# 5Vto3V3Buck.net
KiCad netlist of a schematic drawn in Altium Designer
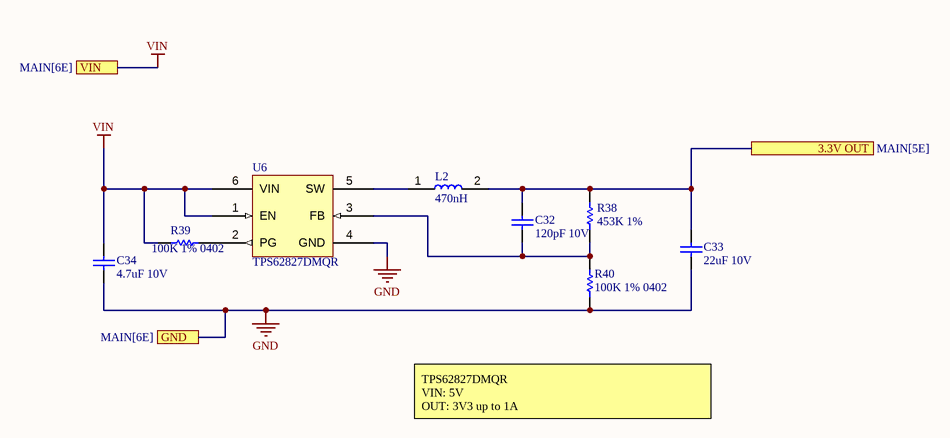
[diagram p0: 5Vto3V3Buck.SchDoc]

(export (version "E")
  (design (tool "Eeschema 10.0.6"))
  (components
    (comp (ref "C32")
      (value "120pF 10V")
      (footprint "CAPC0603(1608)100_N")
      (description "CAP 120pF 10V ±10% 0603 (1608 Metric) Thickness 1mm SMD")
      (fields (field (name "TOLERANCE") "Â±10%"))
      (libsource (lib "Altium Content Vault") (part "CAP"))
    )
    (comp (ref "C33")
      (value "22uF 10V")
      (footprint "CAPC1608X100X20ML10")
      (description "Chip Capacitor, 22 uF, +/- 20%, 10 V, -55 to 85 degC, 0603 (1608 Metric), RoHS, Tape and Reel")
      (fields (field (name "MANUFACTURER") "TDK") (field (name "TOLERANCE") "±20%"))
      (libsource (lib "Altium Content Vault") (part "CAP-NP-2"))
    )
    (comp (ref "C34")
      (value "4.7uF 10V")
      (footprint "CAPC0603(1608)55_N")
      (description "CAP 4.7uF 10V ±10% 0603 (1608 Metric) Thickness 0.55mm SMD")
      (fields (field (name "TOLERANCE") "Â±10%"))
      (libsource (lib "Altium Content Vault") (part "CAP"))
    )
    (comp (ref "L2")
      (value "470nH")
      (footprint "MLP2012SR47MT0S1")
      (description "FIXED IND 470NH 1.2A 90 MOHM SMD")
      (fields (field (name "MP") "MLP2012SR47MT0S1") (field (name "MANUFACTURER") "TDK"))
      (libsource (lib "ESE516A2") (part "MLP2012SR47MT0S1"))
    )
    (comp (ref "R38")
      (value "453K 1%")
      (footprint "RESC0402(1005)_L")
      (description "453K 0.063W 1% 0402 (1005 Metric)  SMD")
      (fields (field (name "TOLERANCE") "1 %") (field (name "POWER") "0.063 W"))
      (libsource (lib "Altium Content Vault") (part "RES"))
    )
    (comp (ref "R39")
      (value "100K 1% 0402")
      (footprint "RESC0402(1005)_M")
      (description "100K 0.063W 1% 0402 (1005 Metric)  SMD")
      (fields (field (name "POWER") "0.063 W") (field (name "TOLERANCE") "1 %"))
      (libsource (lib "Altium Content Vault") (part "RES"))
    )
    (comp (ref "R40")
      (value "100K 1% 0402")
      (footprint "RESC0402(1005)_M")
      (description "100K 0.063W 1% 0402 (1005 Metric)  SMD")
      (fields (field (name "POWER") "0.063 W") (field (name "TOLERANCE") "1 %"))
      (libsource (lib "Altium Content Vault") (part "RES"))
    )
    (comp (ref "U6")
      (value "TPS62827DMQR")
      (footprint "Texas_Instruments_DMQ0006A_MFG")
      (description "2.4V-5.5V input, 4A step-down converter with 1% Accuracy in 1.5mm x 1.5mm QFN 6-VSON-HR -40 to 125")
      (fields (field (name "MANUFACTURER") "Texas Instruments"))
      (libsource (lib "ESE516A2") (part "TPS62827DMQR"))
    )
  )
  (nets
    (net (code "1") (name "/3.3V OUT") (class "Default")
      (node (ref "C32") (pin "2") (pinfunction "2_2") (pintype "passive"))
      (node (ref "C33") (pin "2") (pinfunction "2_2") (pintype "passive"))
      (node (ref "L2") (pin "2") (pinfunction "2_2") (pintype "passive"))
      (node (ref "R38") (pin "1") (pinfunction "1_1") (pintype "passive"))
    )
    (net (code "2") (name "GND") (class "Default")
      (node (ref "C33") (pin "1") (pinfunction "1_1") (pintype "passive"))
      (node (ref "C34") (pin "1") (pinfunction "1_1") (pintype "passive"))
      (node (ref "R40") (pin "1") (pinfunction "1_1") (pintype "passive"))
      (node (ref "U6") (pin "4") (pinfunction "GND_4") (pintype "power_in"))
    )
    (net (code "3") (name "Net-(U6-FB)") (class "Default")
      (node (ref "C32") (pin "1") (pinfunction "1_1") (pintype "passive"))
      (node (ref "R38") (pin "2") (pinfunction "2_2") (pintype "passive"))
      (node (ref "R40") (pin "2") (pinfunction "2_2") (pintype "passive"))
      (node (ref "U6") (pin "3") (pinfunction "FB_3") (pintype "input"))
    )
    (net (code "4") (name "Net-(U6-PG)") (class "Default")
      (node (ref "R39") (pin "2") (pinfunction "2_2") (pintype "passive"))
      (node (ref "U6") (pin "2") (pinfunction "PG_2") (pintype "output"))
    )
    (net (code "5") (name "Net-(U6-SW)") (class "Default")
      (node (ref "L2") (pin "1") (pinfunction "1_1") (pintype "passive"))
      (node (ref "U6") (pin "5") (pinfunction "SW_5") (pintype "power_in"))
    )
    (net (code "6") (name "VIN") (class "Default")
      (node (ref "C34") (pin "2") (pinfunction "2_2") (pintype "passive"))
      (node (ref "R39") (pin "1") (pinfunction "1_1") (pintype "passive"))
      (node (ref "U6") (pin "1") (pinfunction "EN_1") (pintype "input"))
      (node (ref "U6") (pin "6") (pinfunction "VIN_6") (pintype "power_in"))
    )
  )
)
